# Mechanical_and_Interconnect.net
KiCad netlist of a schematic drawn in Altium Designer
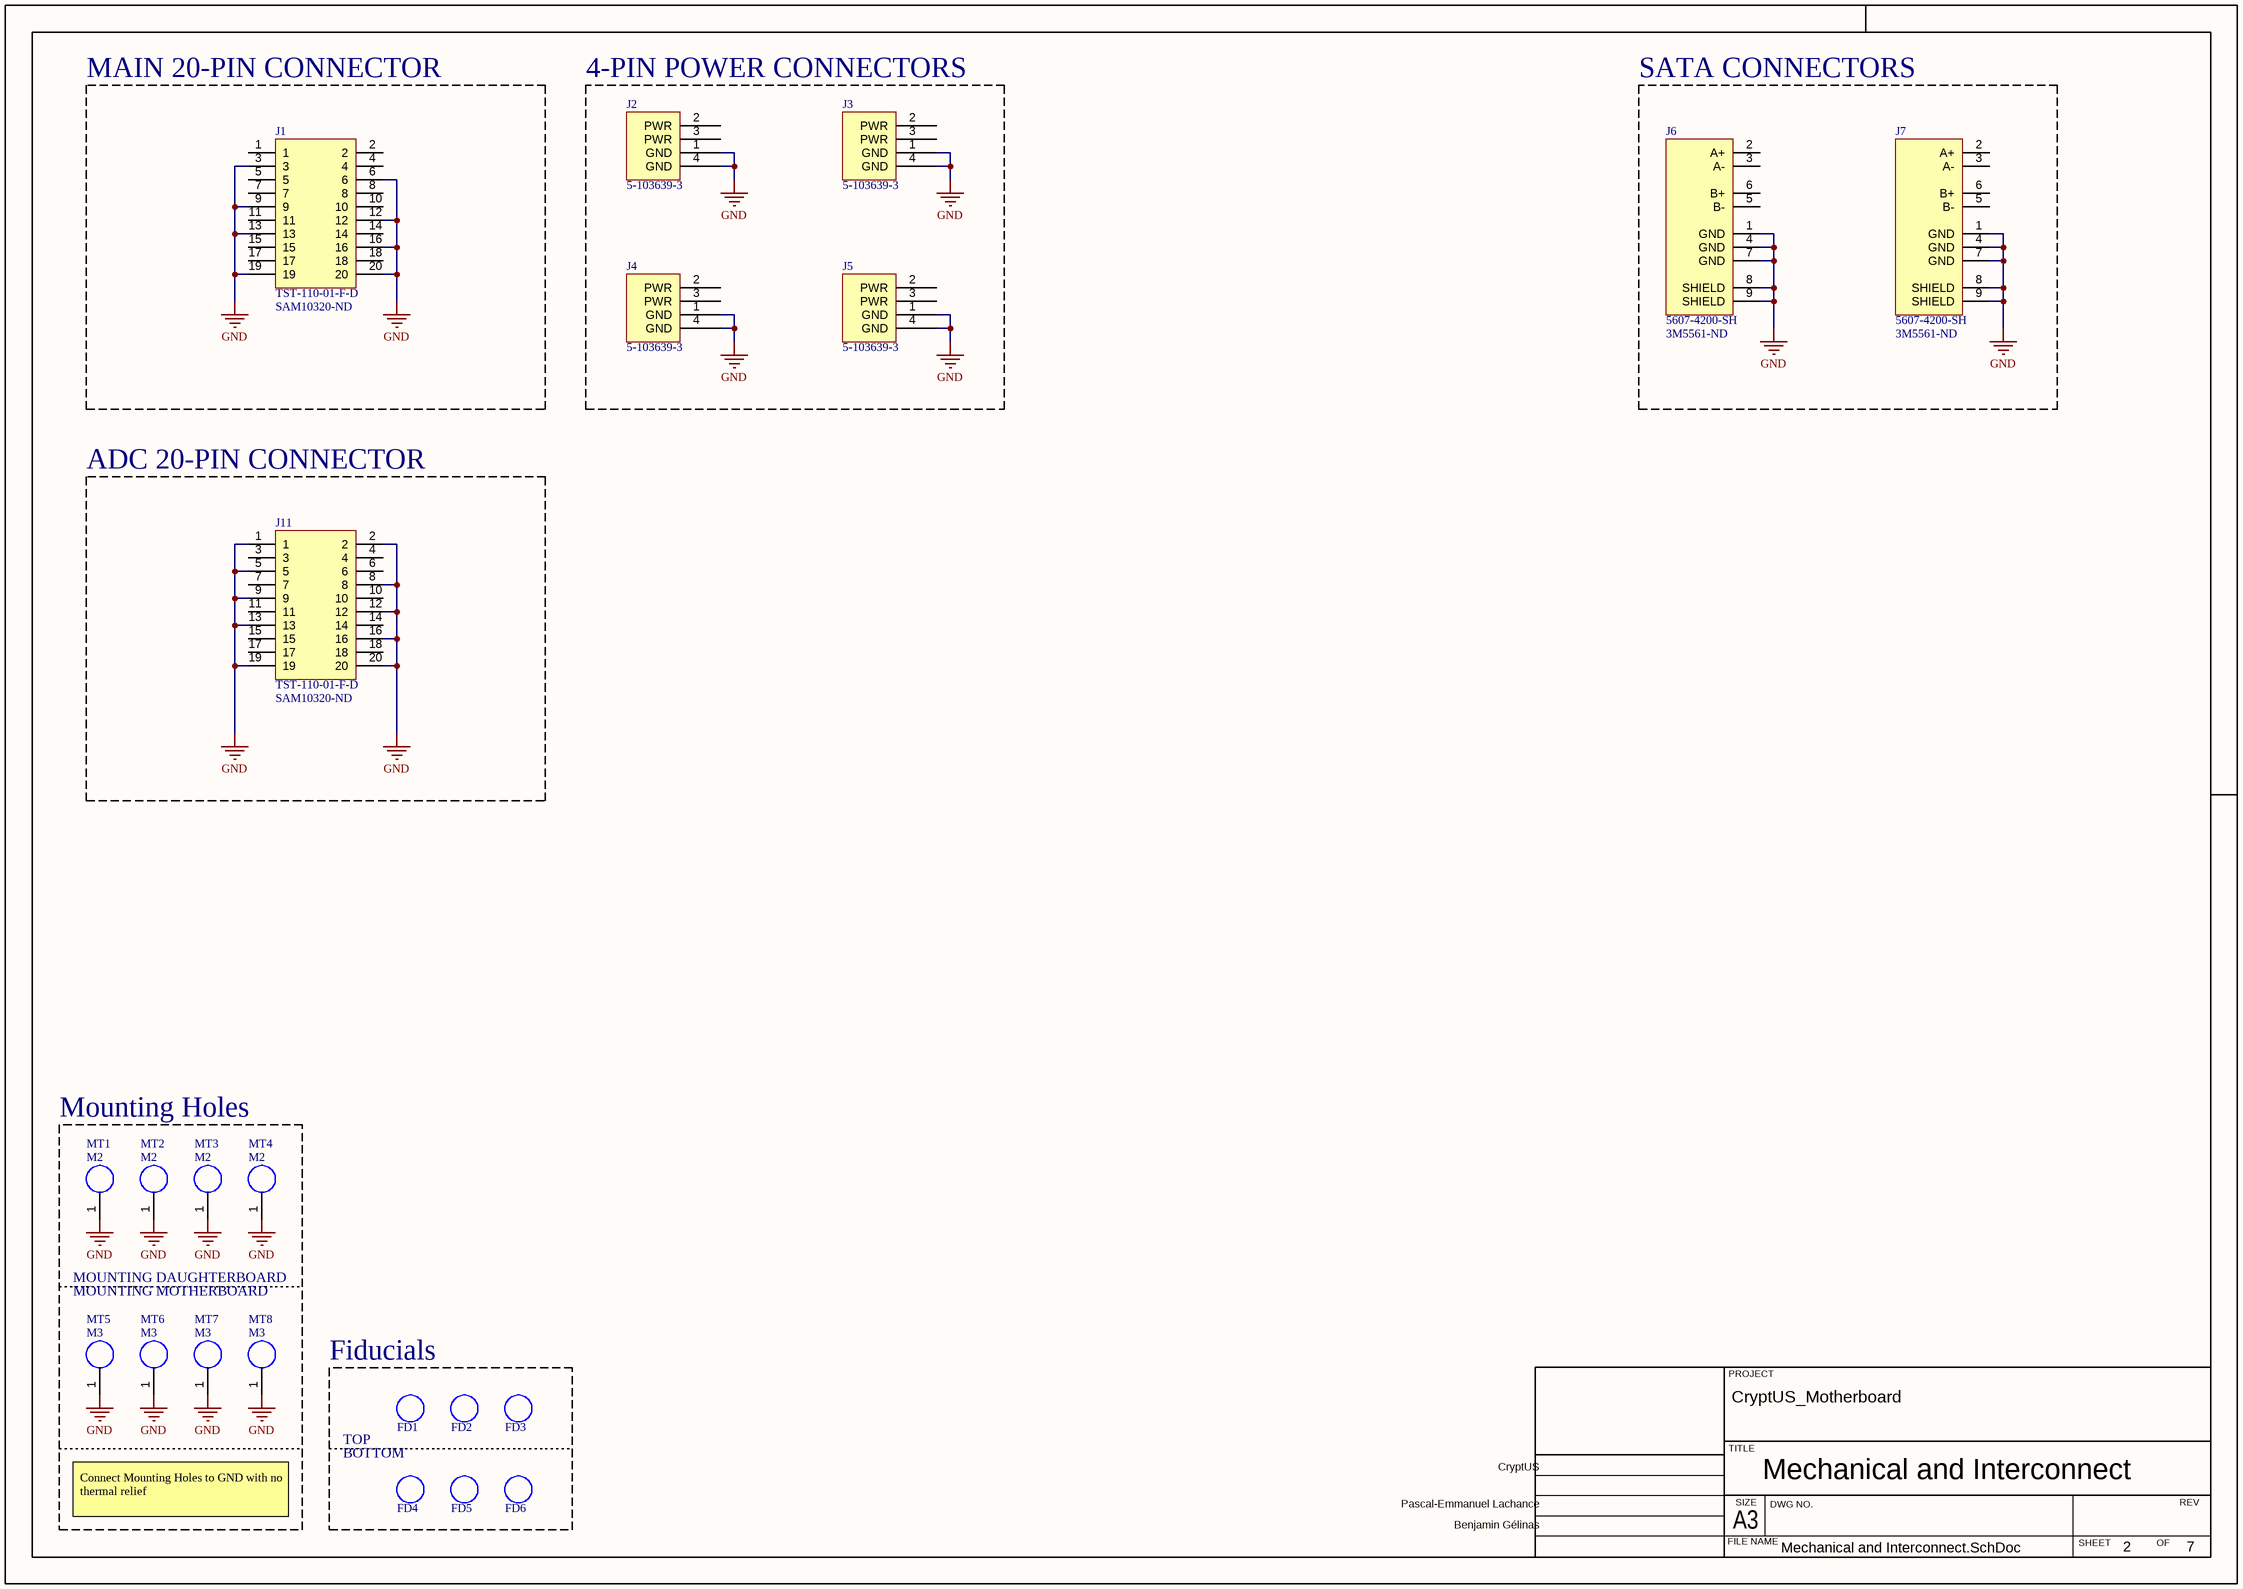
[diagram p0: Mechanical and Interconnect.SchDoc]

(export (version "E")
  (design (tool "Eeschema 10.0.6"))
  (components
    (comp (ref "FD1") (value "FIDUCIAL") (footprint "FIDUCIAL") (libsource (lib "Symbols") (part "FIDUCIAL")))
    (comp (ref "FD2") (value "FIDUCIAL") (footprint "FIDUCIAL") (libsource (lib "Symbols") (part "FIDUCIAL")))
    (comp (ref "FD3") (value "FIDUCIAL") (footprint "FIDUCIAL") (libsource (lib "Symbols") (part "FIDUCIAL")))
    (comp (ref "FD4") (value "FIDUCIAL") (footprint "FIDUCIAL") (libsource (lib "Symbols") (part "FIDUCIAL")))
    (comp (ref "FD5") (value "FIDUCIAL") (footprint "FIDUCIAL") (libsource (lib "Symbols") (part "FIDUCIAL")))
    (comp (ref "FD6") (value "FIDUCIAL") (footprint "FIDUCIAL") (libsource (lib "Symbols") (part "FIDUCIAL")))
    (comp (ref "J1")
      (value "TST-110-01-F-D")
      (footprint "TST-110-01-F-D")
      (description "CONN HEADER VERT 20POS 2.54MM")
      (fields (field (name "MFR") "Samtech Inc.") (field (name "SUPPLIER PART NUMBER 1") "SAM10320-ND"))
      (libsource (lib "CryptLib") (part "CONN_TST-100-01-F-D"))
    )
    (comp (ref "J2")
      (value "5-103639-3")
      (footprint "CryptLib:5-103639-3")
      (description "CONN HEADER VERT 4POS 2.54MM")
      (fields (field (name "MFR") "TE Connectivity"))
      (libsource (lib "CryptLib") (part "CONN_5-103639-3"))
    )
    (comp (ref "J3")
      (value "5-103639-3")
      (footprint "5-103639-3")
      (description "CONN HEADER VERT 4POS 2.54MM")
      (fields (field (name "MFR") "TE Connectivity"))
      (libsource (lib "CryptLib") (part "CONN_5-103639-3"))
    )
    (comp (ref "J4")
      (value "5-103639-3")
      (footprint "5-103639-3")
      (description "CONN HEADER VERT 4POS 2.54MM")
      (fields (field (name "MFR") "TE Connectivity"))
      (libsource (lib "CryptLib") (part "CONN_5-103639-3"))
    )
    (comp (ref "J5")
      (value "5-103639-3")
      (footprint "5-103639-3")
      (description "CONN HEADER VERT 4POS 2.54MM")
      (fields (field (name "MFR") "TE Connectivity"))
      (libsource (lib "CryptLib") (part "CONN_5-103639-3"))
    )
    (comp (ref "J6")
      (value "5607-4200-SH")
      (footprint "CryptLib:5607-4200-SH")
      (description "7 Position SATA Plug Connector Solder Surface Mount, Right Angle")
      (fields (field (name "MFR") "3M") (field (name "SUPPLIER PART NUMBER 1") "3M5561-ND"))
      (libsource (lib "CryptLib") (part "CONN_5607-4200-SH"))
    )
    (comp (ref "J7")
      (value "5607-4200-SH")
      (footprint "CryptLib:5607-4200-SH")
      (description "7 Position SATA Plug Connector Solder Surface Mount, Right Angle")
      (fields (field (name "MFR") "3M") (field (name "SUPPLIER PART NUMBER 1") "3M5561-ND"))
      (libsource (lib "CryptLib") (part "CONN_5607-4200-SH"))
    )
    (comp (ref "J11")
      (value "TST-110-01-F-D")
      (footprint "TST-110-01-F-D")
      (description "CONN HEADER VERT 20POS 2.54MM")
      (fields (field (name "MFR") "Samtech Inc.") (field (name "SUPPLIER PART NUMBER 1") "SAM10320-ND"))
      (libsource (lib "CryptLib") (part "CONN_TST-100-01-F-D"))
    )
    (comp (ref "MT1") (value "M2") (footprint "MTH_M2") (libsource (lib "RaesLib") (part "MOUNTING_HOLE")))
    (comp (ref "MT2") (value "M2") (footprint "MTH_M2") (libsource (lib "RaesLib") (part "MOUNTING_HOLE")))
    (comp (ref "MT3") (value "M2") (footprint "MTH_M2") (libsource (lib "RaesLib") (part "MOUNTING_HOLE")))
    (comp (ref "MT4") (value "M2") (footprint "MTH_M2") (libsource (lib "RaesLib") (part "MOUNTING_HOLE")))
    (comp (ref "MT5") (value "M3") (footprint "MTH_M3") (libsource (lib "RaesLib") (part "MOUNTING_HOLE")))
    (comp (ref "MT6") (value "M3") (footprint "MTH_M3") (libsource (lib "RaesLib") (part "MOUNTING_HOLE")))
    (comp (ref "MT7") (value "M3") (footprint "MTH_M3") (libsource (lib "RaesLib") (part "MOUNTING_HOLE")))
    (comp (ref "MT8") (value "M3") (footprint "MTH_M3") (libsource (lib "RaesLib") (part "MOUNTING_HOLE")))
  )
  (nets
    (net (code "1") (name "GND") (class "Default")
      (node (ref "J1") (pin "12") (pinfunction "12_12") (pintype "passive"))
      (node (ref "J1") (pin "13") (pinfunction "13_13") (pintype "passive"))
      (node (ref "J1") (pin "16") (pinfunction "16_16") (pintype "passive"))
      (node (ref "J1") (pin "19") (pinfunction "19_19") (pintype "passive"))
      (node (ref "J1") (pin "20") (pinfunction "20_20") (pintype "passive"))
      (node (ref "J1") (pin "3") (pinfunction "3_3") (pintype "passive"))
      (node (ref "J1") (pin "6") (pinfunction "6_6") (pintype "passive"))
      (node (ref "J1") (pin "9") (pinfunction "9_9") (pintype "passive"))
      (node (ref "J11") (pin "1") (pinfunction "1_1") (pintype "passive"))
      (node (ref "J11") (pin "12") (pinfunction "12_12") (pintype "passive"))
      (node (ref "J11") (pin "13") (pinfunction "13_13") (pintype "passive"))
      (node (ref "J11") (pin "16") (pinfunction "16_16") (pintype "passive"))
      (node (ref "J11") (pin "19") (pinfunction "19_19") (pintype "passive"))
      (node (ref "J11") (pin "2") (pinfunction "2_2") (pintype "passive"))
      (node (ref "J11") (pin "20") (pinfunction "20_20") (pintype "passive"))
      (node (ref "J11") (pin "5") (pinfunction "5_5") (pintype "passive"))
      (node (ref "J11") (pin "8") (pinfunction "8_8") (pintype "passive"))
      (node (ref "J11") (pin "9") (pinfunction "9_9") (pintype "passive"))
      (node (ref "J2") (pin "1") (pinfunction "GND_1") (pintype "power_in"))
      (node (ref "J2") (pin "4") (pinfunction "GND_4") (pintype "power_in"))
      (node (ref "J3") (pin "1") (pinfunction "GND_1") (pintype "power_in"))
      (node (ref "J3") (pin "4") (pinfunction "GND_4") (pintype "power_in"))
      (node (ref "J4") (pin "1") (pinfunction "GND_1") (pintype "power_in"))
      (node (ref "J4") (pin "4") (pinfunction "GND_4") (pintype "power_in"))
      (node (ref "J5") (pin "1") (pinfunction "GND_1") (pintype "power_in"))
      (node (ref "J5") (pin "4") (pinfunction "GND_4") (pintype "power_in"))
      (node (ref "J6") (pin "1") (pinfunction "GND_1") (pintype "power_in"))
      (node (ref "J6") (pin "4") (pinfunction "GND_4") (pintype "power_in"))
      (node (ref "J6") (pin "7") (pinfunction "GND_7") (pintype "power_in"))
      (node (ref "J6") (pin "8") (pinfunction "SHIELD_8") (pintype "passive"))
      (node (ref "J6") (pin "9") (pinfunction "SHIELD_9") (pintype "passive"))
      (node (ref "J7") (pin "1") (pinfunction "GND_1") (pintype "power_in"))
      (node (ref "J7") (pin "4") (pinfunction "GND_4") (pintype "power_in"))
      (node (ref "J7") (pin "7") (pinfunction "GND_7") (pintype "power_in"))
      (node (ref "J7") (pin "8") (pinfunction "SHIELD_8") (pintype "passive"))
      (node (ref "J7") (pin "9") (pinfunction "SHIELD_9") (pintype "passive"))
      (node (ref "MT1") (pin "1") (pintype "passive"))
      (node (ref "MT2") (pin "1") (pintype "passive"))
      (node (ref "MT3") (pin "1") (pintype "passive"))
      (node (ref "MT4") (pin "1") (pintype "passive"))
      (node (ref "MT5") (pin "1") (pintype "passive"))
      (node (ref "MT6") (pin "1") (pintype "passive"))
      (node (ref "MT7") (pin "1") (pintype "passive"))
      (node (ref "MT8") (pin "1") (pintype "passive"))
    )
    (net (code "2") (name "unconnected-(J1-Pad1)") (class "Default")
      (node (ref "J1") (pin "1") (pinfunction "1_1") (pintype "passive"))
    )
    (net (code "3") (name "unconnected-(J1-Pad2)") (class "Default")
      (node (ref "J1") (pin "2") (pinfunction "2_2") (pintype "passive"))
    )
    (net (code "4") (name "unconnected-(J1-Pad4)") (class "Default")
      (node (ref "J1") (pin "4") (pinfunction "4_4") (pintype "passive"))
    )
    (net (code "5") (name "unconnected-(J1-Pad5)") (class "Default")
      (node (ref "J1") (pin "5") (pinfunction "5_5") (pintype "passive"))
    )
    (net (code "6") (name "unconnected-(J1-Pad7)") (class "Default")
      (node (ref "J1") (pin "7") (pinfunction "7_7") (pintype "passive"))
    )
    (net (code "7") (name "unconnected-(J1-Pad8)") (class "Default")
      (node (ref "J1") (pin "8") (pinfunction "8_8") (pintype "passive"))
    )
    (net (code "8") (name "unconnected-(J1-Pad10)") (class "Default")
      (node (ref "J1") (pin "10") (pinfunction "10_10") (pintype "passive"))
    )
    (net (code "9") (name "unconnected-(J1-Pad11)") (class "Default")
      (node (ref "J1") (pin "11") (pinfunction "11_11") (pintype "passive"))
    )
    (net (code "10") (name "unconnected-(J1-Pad14)") (class "Default")
      (node (ref "J1") (pin "14") (pinfunction "14_14") (pintype "passive"))
    )
    (net (code "11") (name "unconnected-(J1-Pad15)") (class "Default")
      (node (ref "J1") (pin "15") (pinfunction "15_15") (pintype "passive"))
    )
    (net (code "12") (name "unconnected-(J1-Pad17)") (class "Default")
      (node (ref "J1") (pin "17") (pinfunction "17_17") (pintype "passive"))
    )
    (net (code "13") (name "unconnected-(J1-Pad18)") (class "Default")
      (node (ref "J1") (pin "18") (pinfunction "18_18") (pintype "passive"))
    )
    (net (code "14") (name "unconnected-(J2-PWR-Pad2)") (class "Default")
      (node (ref "J2") (pin "2") (pinfunction "PWR_2") (pintype "power_in"))
    )
    (net (code "15") (name "unconnected-(J2-PWR-Pad3)") (class "Default")
      (node (ref "J2") (pin "3") (pinfunction "PWR_3") (pintype "power_in"))
    )
    (net (code "16") (name "unconnected-(J3-PWR-Pad2)") (class "Default")
      (node (ref "J3") (pin "2") (pinfunction "PWR_2") (pintype "power_in"))
    )
    (net (code "17") (name "unconnected-(J3-PWR-Pad3)") (class "Default")
      (node (ref "J3") (pin "3") (pinfunction "PWR_3") (pintype "power_in"))
    )
    (net (code "18") (name "unconnected-(J4-PWR-Pad2)") (class "Default")
      (node (ref "J4") (pin "2") (pinfunction "PWR_2") (pintype "power_in"))
    )
    (net (code "19") (name "unconnected-(J4-PWR-Pad3)") (class "Default")
      (node (ref "J4") (pin "3") (pinfunction "PWR_3") (pintype "power_in"))
    )
    (net (code "20") (name "unconnected-(J5-PWR-Pad2)") (class "Default")
      (node (ref "J5") (pin "2") (pinfunction "PWR_2") (pintype "power_in"))
    )
    (net (code "21") (name "unconnected-(J5-PWR-Pad3)") (class "Default")
      (node (ref "J5") (pin "3") (pinfunction "PWR_3") (pintype "power_in"))
    )
    (net (code "22") (name "unconnected-(J6-A+-Pad2)") (class "Default")
      (node (ref "J6") (pin "2") (pinfunction "A+_2") (pintype "passive"))
    )
    (net (code "23") (name "unconnected-(J6-A--Pad3)") (class "Default")
      (node (ref "J6") (pin "3") (pinfunction "A-_3") (pintype "passive"))
    )
    (net (code "24") (name "unconnected-(J6-B+-Pad6)") (class "Default")
      (node (ref "J6") (pin "6") (pinfunction "B+_6") (pintype "passive"))
    )
    (net (code "25") (name "unconnected-(J6-B--Pad5)") (class "Default")
      (node (ref "J6") (pin "5") (pinfunction "B-_5") (pintype "passive"))
    )
    (net (code "26") (name "unconnected-(J7-A+-Pad2)") (class "Default")
      (node (ref "J7") (pin "2") (pinfunction "A+_2") (pintype "passive"))
    )
    (net (code "27") (name "unconnected-(J7-A--Pad3)") (class "Default")
      (node (ref "J7") (pin "3") (pinfunction "A-_3") (pintype "passive"))
    )
    (net (code "28") (name "unconnected-(J7-B+-Pad6)") (class "Default")
      (node (ref "J7") (pin "6") (pinfunction "B+_6") (pintype "passive"))
    )
    (net (code "29") (name "unconnected-(J7-B--Pad5)") (class "Default")
      (node (ref "J7") (pin "5") (pinfunction "B-_5") (pintype "passive"))
    )
    (net (code "30") (name "unconnected-(J11-Pad3)") (class "Default")
      (node (ref "J11") (pin "3") (pinfunction "3_3") (pintype "passive"))
    )
    (net (code "31") (name "unconnected-(J11-Pad4)") (class "Default")
      (node (ref "J11") (pin "4") (pinfunction "4_4") (pintype "passive"))
    )
    (net (code "32") (name "unconnected-(J11-Pad6)") (class "Default")
      (node (ref "J11") (pin "6") (pinfunction "6_6") (pintype "passive"))
    )
    (net (code "33") (name "unconnected-(J11-Pad7)") (class "Default")
      (node (ref "J11") (pin "7") (pinfunction "7_7") (pintype "passive"))
    )
    (net (code "34") (name "unconnected-(J11-Pad10)") (class "Default")
      (node (ref "J11") (pin "10") (pinfunction "10_10") (pintype "passive"))
    )
    (net (code "35") (name "unconnected-(J11-Pad11)") (class "Default")
      (node (ref "J11") (pin "11") (pinfunction "11_11") (pintype "passive"))
    )
    (net (code "36") (name "unconnected-(J11-Pad14)") (class "Default")
      (node (ref "J11") (pin "14") (pinfunction "14_14") (pintype "passive"))
    )
    (net (code "37") (name "unconnected-(J11-Pad15)") (class "Default")
      (node (ref "J11") (pin "15") (pinfunction "15_15") (pintype "passive"))
    )
    (net (code "38") (name "unconnected-(J11-Pad17)") (class "Default")
      (node (ref "J11") (pin "17") (pinfunction "17_17") (pintype "passive"))
    )
    (net (code "39") (name "unconnected-(J11-Pad18)") (class "Default")
      (node (ref "J11") (pin "18") (pinfunction "18_18") (pintype "passive"))
    )
  )
)
